# TCC_modulo_de_automa_o_Wifi_Rev_1.net
KiCad netlist of a schematic drawn in EAGLE
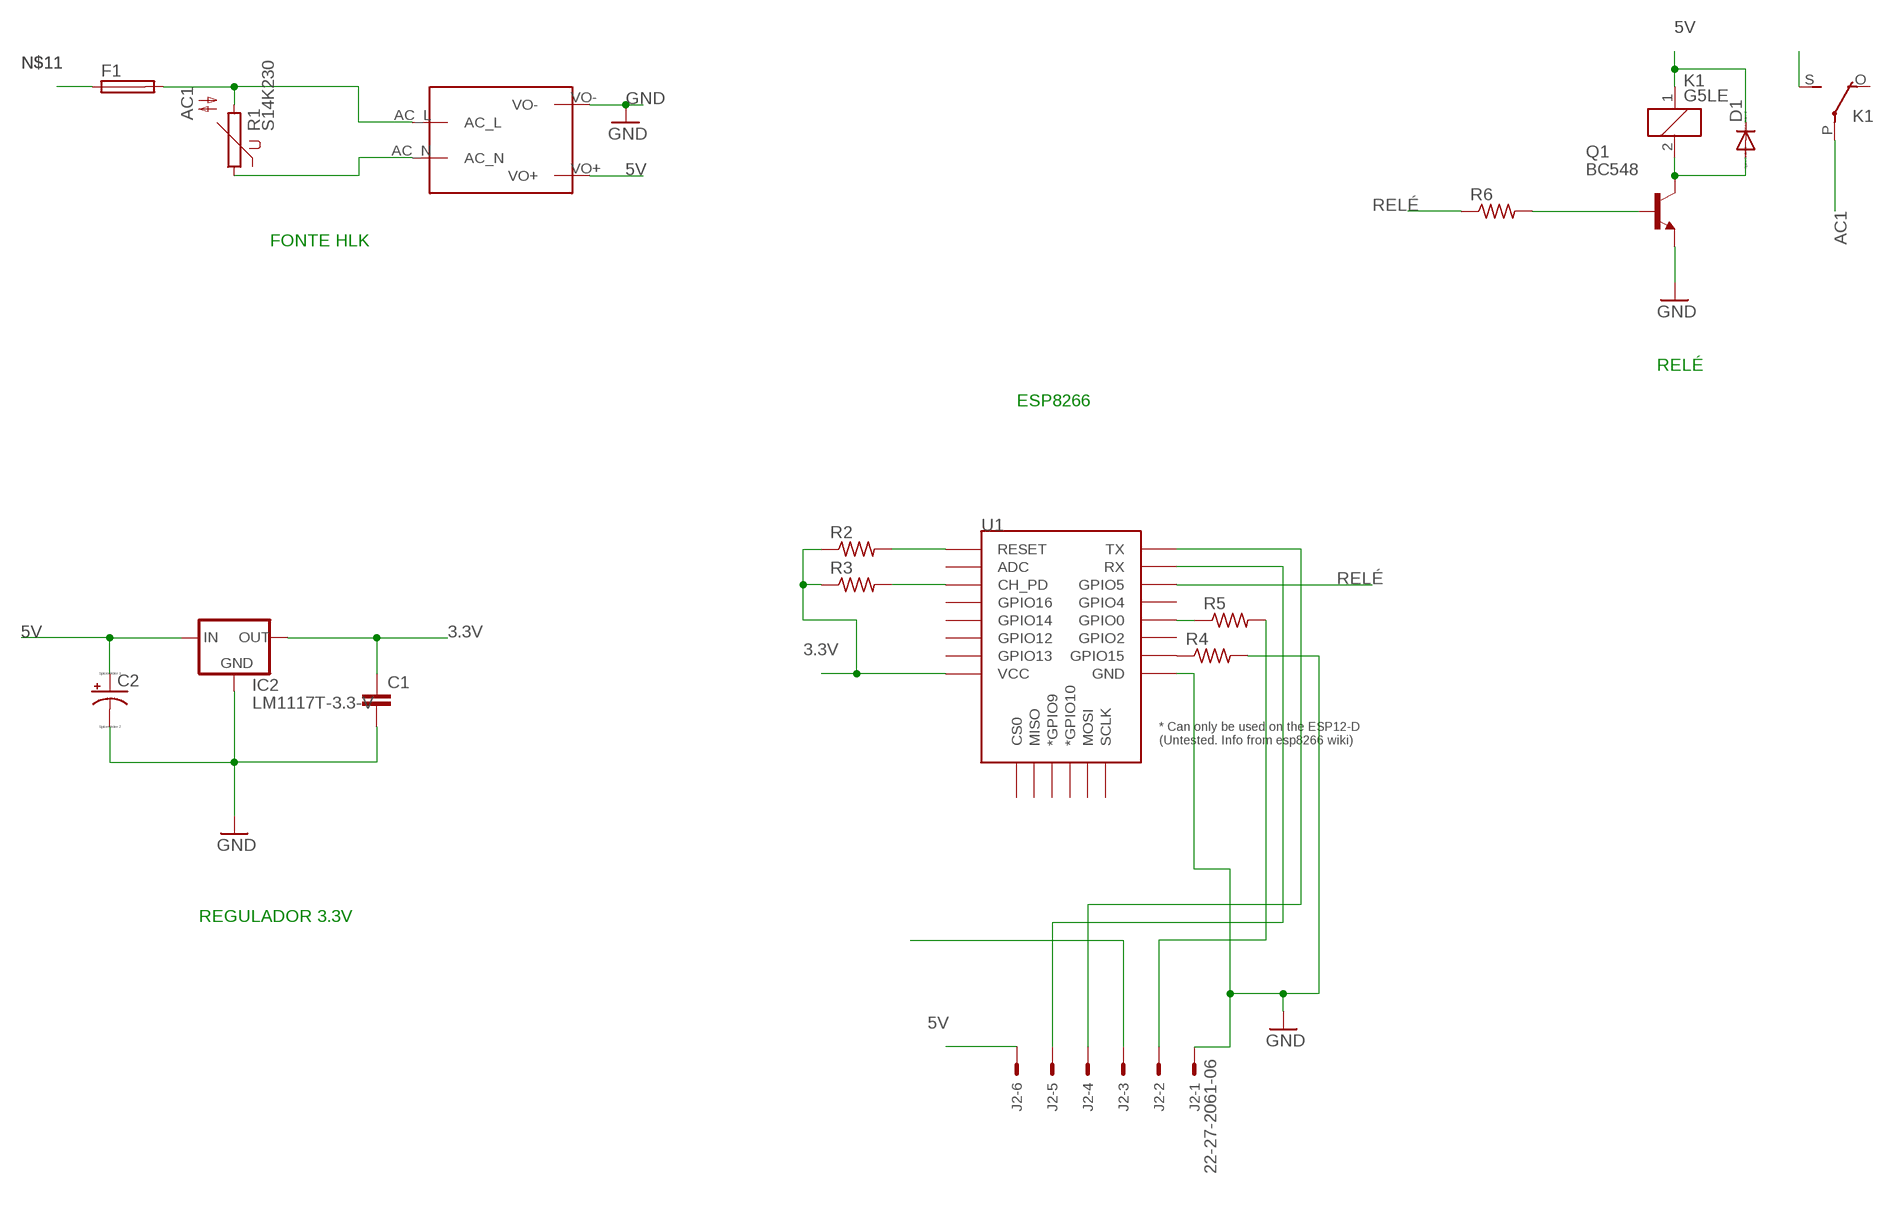
[diagram p0: schematic, sheet 1]

(export (version "E")
  (design (tool "Eeschema 10.0.6"))
  (components
    (comp (ref "C1")
      (value "C-EU050-025X075")
      (footprint "eagle-import:C050-025X075")
      (libsource (lib "eagle-import") (part "C-EU050-025X075"))
    )
    (comp (ref "C2")
      (value "CPOL-USE2-5")
      (footprint "eagle-import:E2-5")
      (libsource (lib "eagle-import") (part "CPOL-USE2-5"))
    )
    (comp (ref "D1")
      (value "DIODE-SOD106A-R")
      (footprint "eagle-import:SOD106A-R")
      (libsource (lib "eagle-import") (part "DIODE-SOD106A-R"))
    )
    (comp (ref "F1")
      (value "GSH15")
      (footprint "eagle-import:GSH15")
      (fields (field (name "MPN") "64900001039"))
      (libsource (lib "eagle-import") (part "GSH15"))
    )
    (comp (ref "IC2")
      (value "LM1117T-3.3-V")
      (footprint "eagle-import:TO220V")
      (libsource (lib "eagle-import") (part "LM1117T--V3.3"))
    )
    (comp (ref "J2")
      (value "22-27-2061-06")
      (footprint "eagle-import:6410-06")
      (libsource (lib "eagle-import") (part "22-?-0627-2061"))
    )
    (comp (ref "K1")
      (value "G5LE")
      (footprint "eagle-import:G5LE")
      (libsource (lib "eagle-import") (part "G5LE"))
    )
    (comp (ref "Q1")
      (value "BC548")
      (footprint "eagle-import:TO92-EBC")
      (libsource (lib "eagle-import") (part "BC548"))
    )
    (comp (ref "R1")
      (value "S14K230")
      (footprint "eagle-import:S14K230")
      (libsource (lib "eagle-import") (part "S14K230"))
    )
    (comp (ref "R2")
      (value "R-US_M0805")
      (footprint "eagle-import:M0805")
      (libsource (lib "eagle-import") (part "R-US_M0805"))
    )
    (comp (ref "R3")
      (value "R-US_M0805")
      (footprint "eagle-import:M0805")
      (libsource (lib "eagle-import") (part "R-US_M0805"))
    )
    (comp (ref "R4")
      (value "R-US_M0805")
      (footprint "eagle-import:M0805")
      (libsource (lib "eagle-import") (part "R-US_M0805"))
    )
    (comp (ref "R5")
      (value "R-US_M0805")
      (footprint "eagle-import:M0805")
      (libsource (lib "eagle-import") (part "R-US_M0805"))
    )
    (comp (ref "R6")
      (value "R-US_M1206")
      (footprint "eagle-import:M1206")
      (libsource (lib "eagle-import") (part "R-US_M1206"))
    )
    (comp (ref "U$2")
      (value "MAINS_CONVERTERS")
      (footprint "eagle-import:HLK-PM01")
      (libsource (lib "eagle-import") (part "MAINS_CONVERTERS"))
    )
    (comp (ref "U1")
      (value "ESP12ESMD")
      (footprint "eagle-import:ESP12E-SMD")
      (libsource (lib "eagle-import") (part "ESP12ESMD"))
    )
  )
  (nets
    (net (code "1") (name "/3.3V") (class "Default")
      (node (ref "C1") (pin "1") (pinfunction "1_1") (pintype "passive"))
      (node (ref "IC2") (pin "2") (pinfunction "OUT_2") (pintype "passive"))
      (node (ref "R2") (pin "1") (pinfunction "1_1") (pintype "passive"))
      (node (ref "R3") (pin "1") (pinfunction "1_1") (pintype "passive"))
      (node (ref "U1") (pin "VCC") (pinfunction "VCC_VCC") (pintype "bidirectional"))
    )
    (net (code "2") (name "/5V") (class "Default")
      (node (ref "C2") (pin "+") (pinfunction "+_+") (pintype "passive"))
      (node (ref "D1") (pin "C") (pinfunction "C_C") (pintype "passive"))
      (node (ref "IC2") (pin "3") (pinfunction "IN_3") (pintype "input"))
      (node (ref "J2") (pin "6") (pinfunction "S_6") (pintype "passive"))
      (node (ref "K1") (pin "1") (pinfunction "1_1") (pintype "passive"))
      (node (ref "U$2") (pin "VO+") (pinfunction "VO+_VO+") (pintype "output"))
    )
    (net (code "3") (name "/AC1") (class "Default")
      (node (ref "F1") (pin "2") (pinfunction "2_2") (pintype "passive"))
      (node (ref "K1") (pin "P") (pinfunction "P_P") (pintype "passive"))
      (node (ref "R1") (pin "2") (pinfunction "2_2") (pintype "passive"))
      (node (ref "U$2") (pin "AC_L") (pinfunction "AC_L_AC_L") (pintype "input"))
    )
    (net (code "4") (name "/N$11") (class "Default")
      (node (ref "F1") (pin "1") (pinfunction "1_1") (pintype "passive"))
    )
    (net (code "5") (name "/RELÉ") (class "Default")
      (node (ref "R6") (pin "1") (pinfunction "1_1") (pintype "passive"))
      (node (ref "U1") (pin "GPIO5") (pinfunction "GPIO5_GPIO5") (pintype "bidirectional"))
    )
    (net (code "6") (name "GND") (class "Default")
      (node (ref "C1") (pin "2") (pinfunction "2_2") (pintype "passive"))
      (node (ref "C2") (pin "-") (pinfunction "-_-") (pintype "passive"))
      (node (ref "IC2") (pin "1") (pinfunction "GND_1") (pintype "input"))
      (node (ref "J2") (pin "1") (pinfunction "S_1") (pintype "passive"))
      (node (ref "Q1") (pin "E") (pinfunction "E_E") (pintype "passive"))
      (node (ref "R4") (pin "2") (pinfunction "2_2") (pintype "passive"))
      (node (ref "U$2") (pin "VO-") (pinfunction "VO-_VO-") (pintype "output"))
      (node (ref "U1") (pin "GND") (pinfunction "GND_GND") (pintype "bidirectional"))
    )
    (net (code "7") (name "Net-(D1-PadA)") (class "Default")
      (node (ref "D1") (pin "A") (pinfunction "A_A") (pintype "passive"))
      (node (ref "K1") (pin "2") (pinfunction "2_2") (pintype "passive"))
      (node (ref "Q1") (pin "C") (pinfunction "C_C") (pintype "passive"))
    )
    (net (code "8") (name "Net-(J2B-S)") (class "Default")
      (node (ref "J2") (pin "2") (pinfunction "S_2") (pintype "passive"))
      (node (ref "R5") (pin "2") (pinfunction "2_2") (pintype "passive"))
    )
    (net (code "9") (name "Net-(J2D-S)") (class "Default")
      (node (ref "J2") (pin "4") (pinfunction "S_4") (pintype "passive"))
      (node (ref "U1") (pin "TXD0") (pinfunction "TX_TXD0") (pintype "bidirectional"))
    )
    (net (code "10") (name "Net-(J2E-S)") (class "Default")
      (node (ref "J2") (pin "5") (pinfunction "S_5") (pintype "passive"))
      (node (ref "U1") (pin "RXD0") (pinfunction "RX_RXD0") (pintype "bidirectional"))
    )
    (net (code "11") (name "Net-(Q1-PadB)") (class "Default")
      (node (ref "Q1") (pin "B") (pinfunction "B_B") (pintype "passive"))
      (node (ref "R6") (pin "2") (pinfunction "2_2") (pintype "passive"))
    )
    (net (code "12") (name "Net-(R1-Pad1)") (class "Default")
      (node (ref "R1") (pin "1") (pinfunction "1_1") (pintype "passive"))
      (node (ref "U$2") (pin "AC_N") (pinfunction "AC_N_AC_N") (pintype "input"))
    )
    (net (code "13") (name "Net-(R2-Pad2)") (class "Default")
      (node (ref "R2") (pin "2") (pinfunction "2_2") (pintype "passive"))
      (node (ref "U1") (pin "RESET") (pinfunction "RESET_RESET") (pintype "bidirectional"))
    )
    (net (code "14") (name "Net-(R3-Pad2)") (class "Default")
      (node (ref "R3") (pin "2") (pinfunction "2_2") (pintype "passive"))
      (node (ref "U1") (pin "CH_PD") (pinfunction "CH_PD_CH_PD") (pintype "bidirectional"))
    )
    (net (code "15") (name "Net-(R4-Pad1)") (class "Default")
      (node (ref "R4") (pin "1") (pinfunction "1_1") (pintype "passive"))
      (node (ref "U1") (pin "GPIO15") (pinfunction "GPIO15_GPIO15") (pintype "bidirectional"))
    )
    (net (code "16") (name "Net-(R5-Pad1)") (class "Default")
      (node (ref "R5") (pin "1") (pinfunction "1_1") (pintype "passive"))
      (node (ref "U1") (pin "GPIO0") (pinfunction "GPIO0_GPIO0") (pintype "bidirectional"))
    )
    (net (code "17") (name "unconnected-(J2C-S-Pad3)") (class "Default")
      (node (ref "J2") (pin "3") (pinfunction "S_3") (pintype "passive"))
    )
    (net (code "18") (name "unconnected-(K1-PadO)") (class "Default")
      (node (ref "K1") (pin "O") (pinfunction "O_O") (pintype "passive"))
    )
    (net (code "19") (name "unconnected-(K1-PadS)") (class "Default")
      (node (ref "K1") (pin "S") (pinfunction "S_S") (pintype "passive"))
    )
    (net (code "20") (name "unconnected-(U1-*GPIO9-PadGPIO9)") (class "Default")
      (node (ref "U1") (pin "GPIO9") (pinfunction "*GPIO9_GPIO9") (pintype "bidirectional"))
    )
    (net (code "21") (name "unconnected-(U1-*GPIO10-PadGPIO10)") (class "Default")
      (node (ref "U1") (pin "GPIO10") (pinfunction "*GPIO10_GPIO10") (pintype "bidirectional"))
    )
    (net (code "22") (name "unconnected-(U1-PadADC)") (class "Default")
      (node (ref "U1") (pin "ADC") (pinfunction "ADC_ADC") (pintype "bidirectional"))
    )
    (net (code "23") (name "unconnected-(U1-PadCS0)") (class "Default")
      (node (ref "U1") (pin "CS0") (pinfunction "CS0_CS0") (pintype "bidirectional"))
    )
    (net (code "24") (name "unconnected-(U1-PadGPIO2)") (class "Default")
      (node (ref "U1") (pin "GPIO2") (pinfunction "GPIO2_GPIO2") (pintype "bidirectional"))
    )
    (net (code "25") (name "unconnected-(U1-PadGPIO4)") (class "Default")
      (node (ref "U1") (pin "GPIO4") (pinfunction "GPIO4_GPIO4") (pintype "bidirectional"))
    )
    (net (code "26") (name "unconnected-(U1-PadGPIO12)") (class "Default")
      (node (ref "U1") (pin "GPIO12") (pinfunction "GPIO12_GPIO12") (pintype "bidirectional"))
    )
    (net (code "27") (name "unconnected-(U1-PadGPIO13)") (class "Default")
      (node (ref "U1") (pin "GPIO13") (pinfunction "GPIO13_GPIO13") (pintype "bidirectional"))
    )
    (net (code "28") (name "unconnected-(U1-PadGPIO14)") (class "Default")
      (node (ref "U1") (pin "GPIO14") (pinfunction "GPIO14_GPIO14") (pintype "bidirectional"))
    )
    (net (code "29") (name "unconnected-(U1-PadGPIO16)") (class "Default")
      (node (ref "U1") (pin "GPIO16") (pinfunction "GPIO16_GPIO16") (pintype "bidirectional"))
    )
    (net (code "30") (name "unconnected-(U1-PadMISO)") (class "Default")
      (node (ref "U1") (pin "MISO") (pinfunction "MISO_MISO") (pintype "bidirectional"))
    )
    (net (code "31") (name "unconnected-(U1-PadMOSI)") (class "Default")
      (node (ref "U1") (pin "MOSI") (pinfunction "MOSI_MOSI") (pintype "bidirectional"))
    )
    (net (code "32") (name "unconnected-(U1-PadSCLK)") (class "Default")
      (node (ref "U1") (pin "SCLK") (pinfunction "SCLK_SCLK") (pintype "bidirectional"))
    )
  )
)
